# STM32F4_Control_Board.net
KiCad netlist of a schematic drawn in Altium Designer
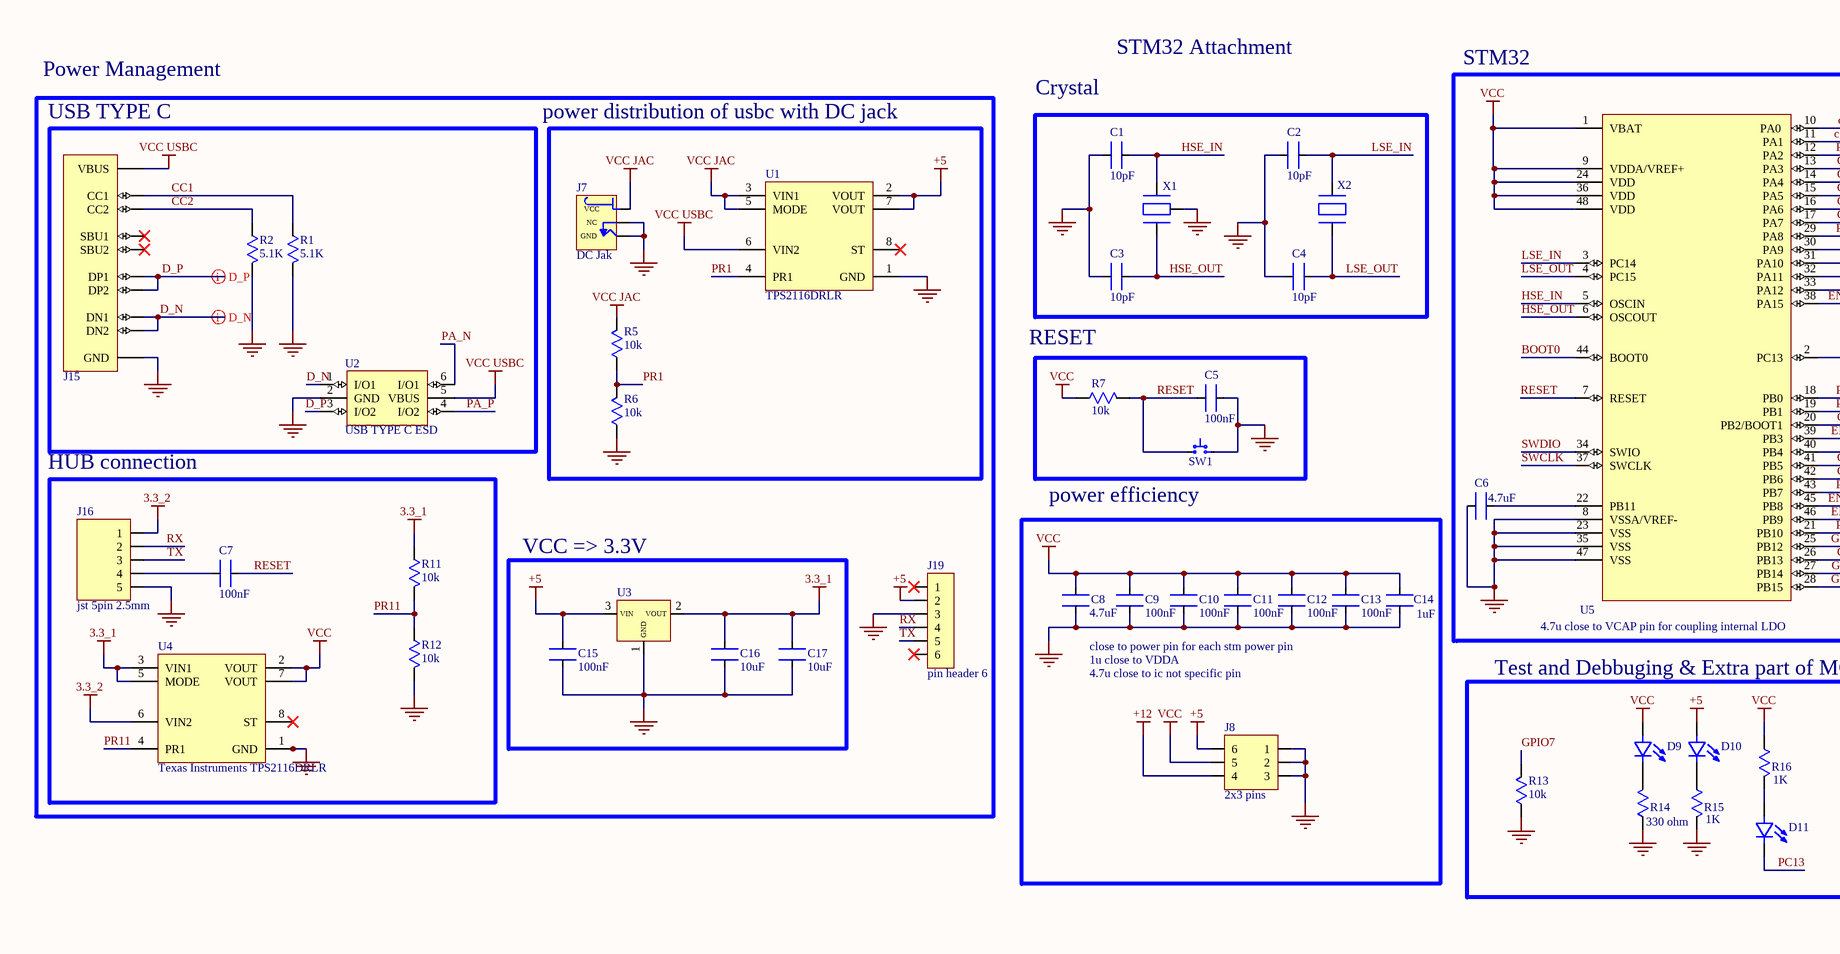
[diagram p0: STM32F4 Control Board.SchDoc, left]
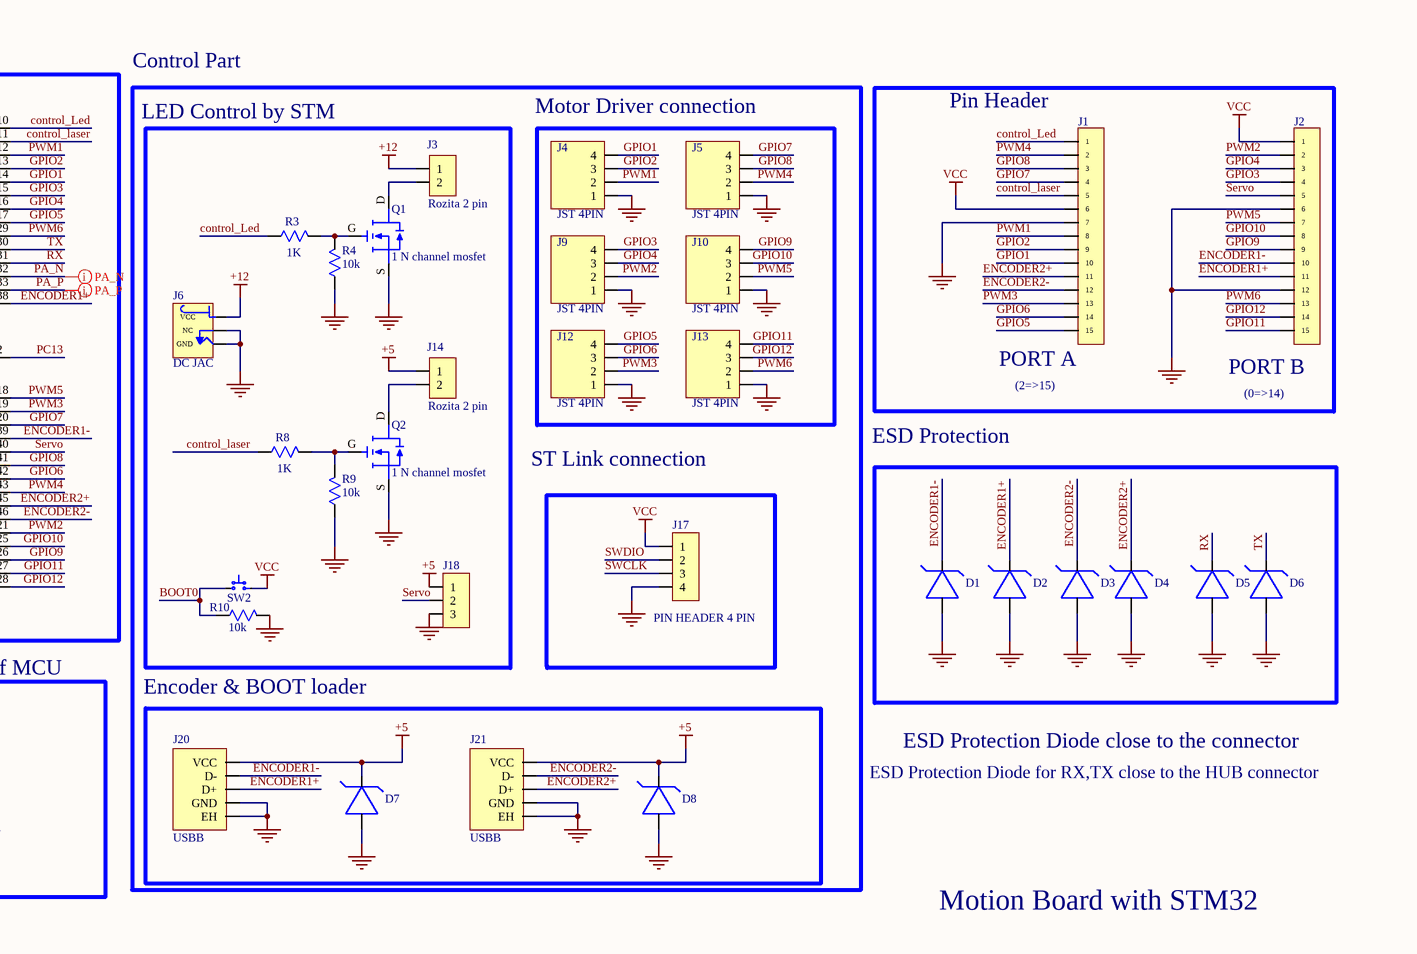
[diagram p1: STM32F4 Control Board.SchDoc, right]

(export (version "E")
  (design (tool "Eeschema 10.0.6"))
  (components
    (comp (ref "C1")
      (value "10pF")
      (footprint "0603 CAP")
      (description "50V 10pF NP0 ±5% 0603 Multilayer Ceramic Capacitors MLCC - SMD/SMT ROHS")
      (fields (field (name "MANUFACTURE PART NUMBER") "CC0603JRNPO9BN100"))
      (libsource (lib "control_ugvc") (part "10pF"))
    )
    (comp (ref "C2")
      (value "10pF")
      (footprint "0603 CAP")
      (description "50V 10pF NP0 ±5% 0603 Multilayer Ceramic Capacitors MLCC - SMD/SMT ROHS")
      (fields (field (name "MANUFACTURE PART NUMBER") "CC0603JRNPO9BN100"))
      (libsource (lib "control_ugvc") (part "10pF"))
    )
    (comp (ref "C3")
      (value "10pF")
      (footprint "0603 CAP")
      (description "50V 10pF NP0 ±5% 0603 Multilayer Ceramic Capacitors MLCC - SMD/SMT ROHS")
      (fields (field (name "MANUFACTURE PART NUMBER") "CC0603JRNPO9BN100"))
      (libsource (lib "control_ugvc") (part "10pF"))
    )
    (comp (ref "C4")
      (value "10pF")
      (footprint "0603 CAP")
      (description "50V 10pF NP0 ±5% 0603 Multilayer Ceramic Capacitors MLCC - SMD/SMT ROHS")
      (fields (field (name "MANUFACTURE PART NUMBER") "CC0603JRNPO9BN100"))
      (libsource (lib "control_ugvc") (part "10pF"))
    )
    (comp (ref "C5")
      (value "100nF")
      (footprint "0603 CAP")
      (description "50V 100nF X7R ±10% 0603 Multilayer Ceramic Capacitors MLCC - SMD/SMT ROHS")
      (fields (field (name "MANUFACTURE PART NUMBER") "CC0603KRX7R9BB104"))
      (libsource (lib "control_ugvc") (part "100nF"))
    )
    (comp (ref "C6")
      (value "4.7uF")
      (footprint "0603 CAP")
      (description "6.3V 4.7uF X5R ±20% 0603 Multilayer Ceramic Capacitors MLCC - SMD/SMT ROHS")
      (fields (field (name "MANUFACTURE PART NUMBER") "CL10A475MQ8NNNC"))
      (libsource (lib "control_ugvc") (part "4.7uF"))
    )
    (comp (ref "C7")
      (value "100nF")
      (footprint "0603 CAP")
      (description "50V 100nF X7R ±10% 0603 Multilayer Ceramic Capacitors MLCC - SMD/SMT ROHS")
      (fields (field (name "MANUFACTURE PART NUMBER") "CC0603KRX7R9BB104"))
      (libsource (lib "control_ugvc") (part "100nF"))
    )
    (comp (ref "C8")
      (value "4.7uF")
      (footprint "0603 CAP")
      (description "6.3V 4.7uF X5R ±20% 0603 Multilayer Ceramic Capacitors MLCC - SMD/SMT ROHS")
      (fields (field (name "MANUFACTURE PART NUMBER") "CL10A475MQ8NNNC"))
      (libsource (lib "control_ugvc") (part "4.7uF"))
    )
    (comp (ref "C9")
      (value "100nF")
      (footprint "0603 CAP")
      (description "50V 100nF X7R ±10% 0603 Multilayer Ceramic Capacitors MLCC - SMD/SMT ROHS")
      (fields (field (name "MANUFACTURE PART NUMBER") "CC0603KRX7R9BB104"))
      (libsource (lib "control_ugvc") (part "100nF"))
    )
    (comp (ref "C10")
      (value "100nF")
      (footprint "0603 CAP")
      (description "50V 100nF X7R ±10% 0603 Multilayer Ceramic Capacitors MLCC - SMD/SMT ROHS")
      (fields (field (name "MANUFACTURE PART NUMBER") "CC0603KRX7R9BB104"))
      (libsource (lib "control_ugvc") (part "100nF"))
    )
    (comp (ref "C11")
      (value "100nF")
      (footprint "0603 CAP")
      (description "50V 100nF X7R ±10% 0603 Multilayer Ceramic Capacitors MLCC - SMD/SMT ROHS")
      (fields (field (name "MANUFACTURE PART NUMBER") "CC0603KRX7R9BB104"))
      (libsource (lib "control_ugvc") (part "100nF"))
    )
    (comp (ref "C12")
      (value "100nF")
      (footprint "0603 CAP")
      (description "50V 100nF X7R ±10% 0603 Multilayer Ceramic Capacitors MLCC - SMD/SMT ROHS")
      (fields (field (name "MANUFACTURE PART NUMBER") "CC0603KRX7R9BB104"))
      (libsource (lib "control_ugvc") (part "100nF"))
    )
    (comp (ref "C13")
      (value "100nF")
      (footprint "0603 CAP")
      (description "50V 100nF X7R ±10% 0603 Multilayer Ceramic Capacitors MLCC - SMD/SMT ROHS")
      (fields (field (name "MANUFACTURE PART NUMBER") "CC0603KRX7R9BB104"))
      (libsource (lib "control_ugvc") (part "100nF"))
    )
    (comp (ref "C14")
      (value "1uF")
      (footprint "0603 CAP")
      (description "16V 1uF X5R ±10% 0603 Multilayer Ceramic Capacitors MLCC - SMD/SMT ROHS")
      (fields (field (name "MANUFACTURE PART NUMBER") "CGA0603X5R105K160JT"))
      (libsource (lib "control_ugvc") (part "1uF"))
    )
    (comp (ref "C15")
      (value "100nF")
      (footprint "0603 CAP")
      (description "50V 100nF X7R ±10% 0603 Multilayer Ceramic Capacitors MLCC - SMD/SMT ROHS")
      (fields (field (name "MANUFACTURE PART NUMBER") "CC0603KRX7R9BB104"))
      (libsource (lib "control_ugvc") (part "100nF"))
    )
    (comp (ref "C16")
      (value "10uF")
      (footprint "0603 CAP")
      (description "6.3V 10uF X5R ±20% 0603 Multilayer Ceramic Capacitors MLCC - SMD/SMT ROHS")
      (fields (field (name "MANUFACTURE PART NUMBER") "CC0603MRX5R5BB106"))
      (libsource (lib "control_ugvc") (part "10uF"))
    )
    (comp (ref "C17")
      (value "10uF")
      (footprint "0603 CAP")
      (description "6.3V 10uF X5R ±20% 0603 Multilayer Ceramic Capacitors MLCC - SMD/SMT ROHS")
      (fields (field (name "MANUFACTURE PART NUMBER") "CC0603MRX5R5BB106"))
      (libsource (lib "control_ugvc") (part "10uF"))
    )
    (comp (ref "D1")
      (value "ESD protection diode")
      (footprint "ESD protection diode")
      (description "SOT-5X3 ESD and Surge Protection (TVS/ESD) ROHS")
      (fields (field (name "MANUFACTURE PART NUMBER") "ESD321DYAR"))
      (libsource (lib "control_ugvc") (part "ESD protection diode"))
    )
    (comp (ref "D2")
      (value "ESD protection diode")
      (footprint "ESD protection diode")
      (description "SOT-5X3 ESD and Surge Protection (TVS/ESD) ROHS")
      (fields (field (name "MANUFACTURE PART NUMBER") "ESD321DYAR"))
      (libsource (lib "control_ugvc") (part "ESD protection diode"))
    )
    (comp (ref "D3")
      (value "ESD protection diode")
      (footprint "ESD protection diode")
      (description "SOT-5X3 ESD and Surge Protection (TVS/ESD) ROHS")
      (fields (field (name "MANUFACTURE PART NUMBER") "ESD321DYAR"))
      (libsource (lib "control_ugvc") (part "ESD protection diode"))
    )
    (comp (ref "D4")
      (value "ESD protection diode")
      (footprint "ESD protection diode")
      (description "SOT-5X3 ESD and Surge Protection (TVS/ESD) ROHS")
      (fields (field (name "MANUFACTURE PART NUMBER") "ESD321DYAR"))
      (libsource (lib "control_ugvc") (part "ESD protection diode"))
    )
    (comp (ref "D5")
      (value "ESD protection diode")
      (footprint "ESD protection diode")
      (description "SOT-5X3 ESD and Surge Protection (TVS/ESD) ROHS")
      (fields (field (name "MANUFACTURE PART NUMBER") "ESD321DYAR"))
      (libsource (lib "control_ugvc") (part "ESD protection diode"))
    )
    (comp (ref "D6")
      (value "ESD protection diode")
      (footprint "ESD protection diode")
      (description "SOT-5X3 ESD and Surge Protection (TVS/ESD) ROHS")
      (fields (field (name "MANUFACTURE PART NUMBER") "ESD321DYAR"))
      (libsource (lib "control_ugvc") (part "ESD protection diode"))
    )
    (comp (ref "D7")
      (value "ESD protection diode")
      (footprint "ESD protection diode")
      (description "SOT-5X3 ESD and Surge Protection (TVS/ESD) ROHS")
      (fields (field (name "MANUFACTURE PART NUMBER") "ESD321DYAR"))
      (libsource (lib "control_ugvc") (part "ESD protection diode"))
    )
    (comp (ref "D8")
      (value "ESD protection diode")
      (footprint "ESD protection diode")
      (description "SOT-5X3 ESD and Surge Protection (TVS/ESD) ROHS")
      (fields (field (name "MANUFACTURE PART NUMBER") "ESD321DYAR"))
      (libsource (lib "control_ugvc") (part "ESD protection diode"))
    )
    (comp (ref "D9")
      (value "RED led")
      (footprint "led 0805")
      (description "20mA 8mcd Colorless Transparent Lens 617nm Red 2V 0805 LED Indication - Discrete ROHS")
      (fields (field (name "MANUFACTURE PART NUMBER") "APT2012EC"))
      (libsource (lib "control_ugvc") (part "RED LED"))
    )
    (comp (ref "D10")
      (value "RED led")
      (footprint "led 0805")
      (description "20mA 8mcd Colorless Transparent Lens 617nm Red 2V 0805 LED Indication - Discrete ROHS")
      (fields (field (name "MANUFACTURE PART NUMBER") "APT2012EC"))
      (libsource (lib "control_ugvc") (part "RED LED"))
    )
    (comp (ref "D11")
      (value "RED led")
      (footprint "led 0805")
      (description "20mA 8mcd Colorless Transparent Lens 617nm Red 2V 0805 LED Indication - Discrete ROHS")
      (fields (field (name "MANUFACTURE PART NUMBER") "APT2012EC"))
      (libsource (lib "control_ugvc") (part "RED LED"))
    )
    (comp (ref "J1")
      (value "pin header 15 pin")
      (footprint "pin headers 15 pin")
      (fields (field (name "MANUFACTURE PART NUMBER") "ZX-PZ2.54-1-15PZZ"))
      (libsource (lib "control_ugvc") (part "pin header 15 pin"))
    )
    (comp (ref "J2")
      (value "pin header 15 pin")
      (footprint "pin headers 15 pin")
      (fields (field (name "MANUFACTURE PART NUMBER") "ZX-PZ2.54-1-15PZZ"))
      (libsource (lib "control_ugvc") (part "pin header 15 pin"))
    )
    (comp (ref "J3")
      (value "Rozita 2 pin")
      (footprint "Rozita")
      (fields (field (name "MANUFACTURE PART NUMBER") "DB128L-5.08-2P-GN-S"))
      (libsource (lib "control_ugvc") (part "Rozita 2 pin"))
    )
    (comp (ref "J4")
      (value "JST 4PIN")
      (footprint "JST 4PIN")
      (fields (field (name "MANUFACTURE PART NUMBER") "HC-XH-4A-TW"))
      (libsource (lib "control_ugvc") (part "JST 4PIN"))
    )
    (comp (ref "J5")
      (value "JST 4PIN")
      (footprint "JST 4PIN")
      (fields (field (name "MANUFACTURE PART NUMBER") "HC-XH-4A-TW"))
      (libsource (lib "control_ugvc") (part "JST 4PIN"))
    )
    (comp (ref "J6")
      (value "DC JAC")
      (footprint "DC Jack")
      (description "Bend-in DC Power Receptacle -20℃~+70℃ 2.5mm 6.5mm 5A 24V Plugin DC Power Connectors ROHS")
      (fields (field (name "MANUFACTURE PART NUMBER") "DC-005-5A-2.5"))
      (libsource (lib "control_ugvc") (part "DC Jak"))
    )
    (comp (ref "J7")
      (value "DC Jak")
      (footprint "DC Jack")
      (description "Bend-in DC Power Receptacle -20℃~+70℃ 2.5mm 6.5mm 5A 24V Plugin DC Power Connectors ROHS")
      (fields (field (name "MANUFACTURE PART NUMBER") "DC-005-5A-2.5"))
      (libsource (lib "control_ugvc") (part "DC Jak"))
    )
    (comp (ref "J8")
      (value "2x3 pins")
      (footprint "2x3 pins")
      (description "Straight 2.54mm 6mm 6P 3mm 2.54mm 双排 2x3P Plugin,P=2.54mm Pin Headers ROHS")
      (fields (field (name "MANUFACTURER") "HanElectricity") (field (name "MFR. PART #") "2541WV-2x03P"))
      (libsource (lib "control_ugvc") (part "2x3 pins"))
    )
    (comp (ref "J9")
      (value "JST 4PIN")
      (footprint "JST 4PIN")
      (fields (field (name "MANUFACTURE PART NUMBER") "HC-XH-4A-TW"))
      (libsource (lib "control_ugvc") (part "JST 4PIN"))
    )
    (comp (ref "J10")
      (value "JST 4PIN")
      (footprint "JST 4PIN")
      (fields (field (name "MANUFACTURE PART NUMBER") "HC-XH-4A-TW"))
      (libsource (lib "control_ugvc") (part "JST 4PIN"))
    )
    (comp (ref "J12")
      (value "JST 4PIN")
      (footprint "JST 4PIN")
      (fields (field (name "MANUFACTURE PART NUMBER") "HC-XH-4A-TW"))
      (libsource (lib "control_ugvc") (part "JST 4PIN"))
    )
    (comp (ref "J13")
      (value "JST 4PIN")
      (footprint "JST 4PIN")
      (fields (field (name "MANUFACTURE PART NUMBER") "HC-XH-4A-TW"))
      (libsource (lib "control_ugvc") (part "JST 4PIN"))
    )
    (comp (ref "J14")
      (value "Rozita 2 pin")
      (footprint "Rozita")
      (fields (field (name "MANUFACTURE PART NUMBER") "DB128L-5.08-2P-GN-S"))
      (libsource (lib "control_ugvc") (part "Rozita 2 pin"))
    )
    (comp (ref "J15")
      (value "USB TYPE-C-31-M-12")
      (footprint "USB Type-C")
      (description "5A 1 16P Female Type-C SMD USB Connectors ROHS")
      (fields (field (name "MANUFACTURE PART NUMBER") "TYPE-C-31-M-12"))
      (libsource (lib "control_ugvc") (part "USB TYPE-C-31-M-12"))
    )
    (comp (ref "J16")
      (value "jst 5pin 2.5mm")
      (footprint "JST 5 PIN 2.5 MM")
      (fields (field (name "MANUFACTURE PART NUMBER") "B5B-XH-A(LF)(SN)"))
      (libsource (lib "control_ugvc") (part "jst 5pin 2.5mm"))
    )
    (comp (ref "J17")
      (value "PIN HEADER 4 PIN")
      (footprint "pin header 4PIN")
      (description "3A Policy 2.5mm 6mm 4P -40℃~+105℃ 2.54mm Single Row 1x4P Plugin,P=2.54mm Pin Headers ROHS")
      (fields (field (name "MANUFACTURE PART NUMBER") "A254UP-ZD04P"))
      (libsource (lib "control_ugvc") (part "PIN HEADER 4 PIN"))
    )
    (comp (ref "J18")
      (value "Plugin,P=2.54mm")
      (footprint "pin header 3 pin")
      (description "3A Straight 3P -65℃~+125℃ 2.54mm Black Single Row Phosphor Bronze Plugin,P=2.54mm Pin Headers ROHS")
      (fields (field (name "MANUFACTURE PART NUMBER") "68001-203HLF"))
      (libsource (lib "control_ugvc") (part "Pin Header 3pin"))
    )
    (comp (ref "J19")
      (value "pin header 6")
      (footprint "pin header 6 pin")
      (fields (field (name "MANUFACTURE PART NUMBER") "PZ254V-11-06P"))
      (libsource (lib "control_ugvc") (part "pin header 6"))
    )
    (comp (ref "J20")
      (value "USBB")
      (footprint "USBB")
      (description "USB 2.0 1 4P Female Type-B Plugin USB Connectors ROHS")
      (fields (field (name "MANUFACTURE PART NUMBER") "U-USBBR04P-F000"))
      (libsource (lib "control_ugvc") (part "USBB R04P-F000"))
    )
    (comp (ref "J21")
      (value "USBB")
      (footprint "USBB")
      (description "USB 2.0 1 4P Female Type-B Plugin USB Connectors ROHS")
      (fields (field (name "MANUFACTURE PART NUMBER") "U-USBBR04P-F000"))
      (libsource (lib "control_ugvc") (part "USBB R04P-F000"))
    )
    (comp (ref "Q1")
      (value "1 N channel mosfet")
      (footprint "1 N channel mosfet")
      (description "20V 7A 1.25W 10mΩ@4.5V,7A 500mV 1 N-channel SOT-23-3L MOSFETs ROHS")
      (fields (field (name "MANUFACTURE PART NUMBER") "SP20N09T1"))
      (libsource (lib "control_ugvc") (part "1 N channel mosfet"))
    )
    (comp (ref "Q2")
      (value "1 N channel mosfet")
      (footprint "1 N channel mosfet")
      (description "20V 7A 1.25W 10mΩ@4.5V,7A 500mV 1 N-channel SOT-23-3L MOSFETs ROHS")
      (fields (field (name "MANUFACTURE PART NUMBER") "SP20N09T1"))
      (libsource (lib "control_ugvc") (part "1 N channel mosfet"))
    )
    (comp (ref "R1")
      (value "5.1K")
      (footprint "0603 RES")
      (description "100mW Thin Film Resistor 75V ±25ppm/℃ ±0.1% 5.1kΩ 0603 Chip Resistor - Surface Mount ROHS")
      (fields (field (name "MANUFACTURE PART NUMBER") "RT0603BRD075K1L"))
      (libsource (lib "control_ugvc") (part "RES 5.1 K"))
    )
    (comp (ref "R2")
      (value "5.1K")
      (footprint "0603 RES")
      (description "100mW Thin Film Resistor 75V ±25ppm/℃ ±0.1% 5.1kΩ 0603 Chip Resistor - Surface Mount ROHS")
      (fields (field (name "MANUFACTURE PART NUMBER") "RT0603BRD075K1L"))
      (libsource (lib "control_ugvc") (part "RES 5.1 K"))
    )
    (comp (ref "R3")
      (value "1K")
      (footprint "0603 RES")
      (description "100mW Thick Film Resistors 75V ±100ppm/℃ ±5% 1kΩ 0603 Chip Resistor - Surface Mount ROHS")
      (fields (field (name "MANUFACTURE PART NUMBER") "FRC0603J102 TS"))
      (libsource (lib "control_ugvc") (part "RES 1K ohm"))
    )
    (comp (ref "R4")
      (value "10k")
      (footprint "0603 RES")
      (description "100mW Thin Film Resistor 75V ±25ppm/℃ ±0.1% 10kΩ 0603 Chip Resistor - Surface Mount ROHS")
      (fields (field (name "MANUFACTURE PART NUMBER") "RT0603BRD0710KL"))
      (libsource (lib "control_ugvc") (part "RES 10kohm"))
    )
    (comp (ref "R5")
      (value "10k")
      (footprint "0603 RES")
      (description "100mW Thin Film Resistor 75V ±25ppm/℃ ±0.1% 10kΩ 0603 Chip Resistor - Surface Mount ROHS")
      (fields (field (name "MANUFACTURE PART NUMBER") "RT0603BRD0710KL"))
      (libsource (lib "control_ugvc") (part "RES 10kohm"))
    )
    (comp (ref "R6")
      (value "10k")
      (footprint "0603 RES")
      (description "100mW Thin Film Resistor 75V ±25ppm/℃ ±0.1% 10kΩ 0603 Chip Resistor - Surface Mount ROHS")
      (fields (field (name "MANUFACTURE PART NUMBER") "RT0603BRD0710KL"))
      (libsource (lib "control_ugvc") (part "RES 10kohm"))
    )
    (comp (ref "R7")
      (value "10k")
      (footprint "0603 RES")
      (description "100mW Thin Film Resistor 75V ±25ppm/℃ ±0.1% 10kΩ 0603 Chip Resistor - Surface Mount ROHS")
      (fields (field (name "MANUFACTURE PART NUMBER") "RT0603BRD0710KL"))
      (libsource (lib "control_ugvc") (part "RES 10kohm"))
    )
    (comp (ref "R8")
      (value "1K")
      (footprint "0603 RES")
      (description "100mW Thick Film Resistors 75V ±100ppm/℃ ±5% 1kΩ 0603 Chip Resistor - Surface Mount ROHS")
      (fields (field (name "MANUFACTURE PART NUMBER") "FRC0603J102 TS"))
      (libsource (lib "control_ugvc") (part "RES 1K ohm"))
    )
    (comp (ref "R9")
      (value "10k")
      (footprint "0603 RES")
      (description "100mW Thin Film Resistor 75V ±25ppm/℃ ±0.1% 10kΩ 0603 Chip Resistor - Surface Mount ROHS")
      (fields (field (name "MANUFACTURE PART NUMBER") "RT0603BRD0710KL"))
      (libsource (lib "control_ugvc") (part "RES 10kohm"))
    )
    (comp (ref "R10")
      (value "10k")
      (footprint "0603 RES")
      (description "100mW Thin Film Resistor 75V ±25ppm/℃ ±0.1% 10kΩ 0603 Chip Resistor - Surface Mount ROHS")
      (fields (field (name "MANUFACTURE PART NUMBER") "RT0603BRD0710KL"))
      (libsource (lib "control_ugvc") (part "RES 10kohm"))
    )
    (comp (ref "R11")
      (value "10k")
      (footprint "0603 RES")
      (description "100mW Thin Film Resistor 75V ±25ppm/℃ ±0.1% 10kΩ 0603 Chip Resistor - Surface Mount ROHS")
      (fields (field (name "MANUFACTURE PART NUMBER") "RT0603BRD0710KL"))
      (libsource (lib "control_ugvc") (part "RES 10kohm"))
    )
    (comp (ref "R12")
      (value "10k")
      (footprint "0603 RES")
      (description "100mW Thin Film Resistor 75V ±25ppm/℃ ±0.1% 10kΩ 0603 Chip Resistor - Surface Mount ROHS")
      (fields (field (name "MANUFACTURE PART NUMBER") "RT0603BRD0710KL"))
      (libsource (lib "control_ugvc") (part "RES 10kohm"))
    )
    (comp (ref "R13")
      (value "10k")
      (footprint "0603 RES")
      (description "100mW Thin Film Resistor 75V ±25ppm/℃ ±0.1% 10kΩ 0603 Chip Resistor - Surface Mount ROHS")
      (fields (field (name "MANUFACTURE PART NUMBER") "RT0603BRD0710KL"))
      (libsource (lib "control_ugvc") (part "RES 10kohm"))
    )
    (comp (ref "R14")
      (value "330 ohm")
      (footprint "0603 RES")
      (description "100mW Thick Film Resistors 75V ±100ppm/℃ ±5% 330Ω 0603 Chip Resistor - Surface Mount ROHS")
      (fields (field (name "MANUFACTURE PART NUMBER") "FRC0603J331 TS"))
      (libsource (lib "control_ugvc") (part "RES 330 ohm"))
    )
    (comp (ref "R15")
      (value "1K")
      (footprint "0603 RES")
      (description "100mW Thick Film Resistors 75V ±100ppm/℃ ±5% 1kΩ 0603 Chip Resistor - Surface Mount ROHS")
      (fields (field (name "MANUFACTURE PART NUMBER") "FRC0603J102 TS"))
      (libsource (lib "control_ugvc") (part "RES 1K ohm"))
    )
    (comp (ref "R16")
      (value "1K")
      (footprint "0603 RES")
      (description "100mW Thick Film Resistors 75V ±100ppm/℃ ±5% 1kΩ 0603 Chip Resistor - Surface Mount ROHS")
      (fields (field (name "MANUFACTURE PART NUMBER") "FRC0603J102 TS"))
      (libsource (lib "control_ugvc") (part "RES 1K ohm"))
    )
    (comp (ref "SW1")
      (value "push button")
      (footprint "Push button")
      (fields (field (name "MANUFACTURE PART NUMBER") "1TS002E-2500-2500-CT"))
      (libsource (lib "control_ugvc") (part "push button"))
    )
    (comp (ref "SW2")
      (value "push button")
      (footprint "Push button")
      (fields (field (name "MANUFACTURE PART NUMBER") "1TS002E-2500-2500-CT"))
      (libsource (lib "control_ugvc") (part "push button"))
    )
    (comp (ref "U1")
      (value "TPS2116DRLR")
      (footprint "power distribution")
      (description "1.6V~5.5V 42mΩ 2.5A 1 SOT-583 Power Distribution Switches ROHS")
      (libsource (lib "control_ugvc") (part "power distribution"))
    )
    (comp (ref "U2")
      (value "USB TYPE C ESD")
      (footprint "usb c esd")
      (description "SOT-23-6 ESD and Surge Protection (TVS/ESD) ROHS")
      (fields (field (name "MANUFACTURE PART NUMBER") "TPUSBLC6-2SC6"))
      (libsource (lib "control_ugvc") (part "usb tybc esd"))
    )
    (comp (ref "U3")
      (value "ST LDO 3.3 regulator")
      (footprint "ST_LDO")
      (fields (field (name "MANUFACTURE PART NUMBER") "LD1117AS33TR"))
      (libsource (lib "control_ugvc") (part "ST LDO 3.3 regulator"))
    )
    (comp (ref "U4")
      (value "Texas Instruments TPS2116DRLR")
      (footprint "power distribution")
      (description "1.6V~5.5V 42mΩ 2.5A 1 SOT-583 Power Distribution Switches ROHS")
      (fields (field (name "MANUFACTURE PART NUMBER") "TPS2116DRLR"))
      (libsource (lib "control_ugvc") (part "power distribution"))
    )
    (comp (ref "U5")
      (value "High-performance basic series ARM Cortex-M4 MCU with DSP and FPU, featuring 512 KB Flash, 100 MHz CPU, and ART accelerator")
      (footprint "Stm32 UFQFPN-48")
      (description "ARM-M4 100MHz UFQFPN-48(7x7) Microcontrollers (MCU/MPU/SOC) ROHS")
      (fields (field (name "MANUFACTURE  PART NUMBER") "STM32F411CEU6"))
      (libsource (lib "control_ugvc") (part "STMicroelectronics STM32F411CEU6"))
    )
    (comp (ref "X1")
      (value "Shenzhen SCTF Elec SX3B25.000F0810G30")
      (footprint "25MHZ Crystal Oscillators")
      (description "25MHz Surface Mount Crystal 8pF ±10ppm ±30ppm SMD3225-4P Crystals ROHS")
      (fields (field (name "MANUFACTURE PART NUMBER") "SX3B25.000F0810G30"))
      (libsource (lib "control_ugvc") (part "25MHZ Crystal oscillator"))
    )
    (comp (ref "X2")
      (value "Seiko Epson X1A0000610006")
      (footprint "32.768 KHZ Crystal oscillator")
      (description "32.768kHz Surface Mount Crystal 7pF ±20ppm SMD2012-2P Crystals ROHSS.")
      (fields (field (name "MANUFACTURE PART NUMBER") "X1A0000610006"))
      (libsource (lib "control_ugvc") (part "32.768 KHZ Crystal oscillator"))
    )
  )
  (nets
    (net (code "1") (name "+5") (class "Default")
      (node (ref "C15") (pin "2") (pinfunction "2_2") (pintype "passive"))
      (node (ref "D10") (pin "1") (pinfunction "1_1") (pintype "passive"))
      (node (ref "D7") (pin "2") (pinfunction "2_2") (pintype "passive"))
      (node (ref "D8") (pin "2") (pinfunction "2_2") (pintype "passive"))
      (node (ref "J14") (pin "1") (pinfunction "1_1") (pintype "passive"))
      (node (ref "J18") (pin "1") (pinfunction "1_1") (pintype "passive"))
      (node (ref "J19") (pin "2") (pinfunction "2_2") (pintype "passive"))
      (node (ref "J20") (pin "1") (pinfunction "VCC_1") (pintype "power_in"))
      (node (ref "J21") (pin "1") (pinfunction "VCC_1") (pintype "power_in"))
      (node (ref "J8") (pin "6") (pinfunction "6_6") (pintype "passive"))
      (node (ref "U1") (pin "2") (pinfunction "VOUT_2") (pintype "power_in"))
      (node (ref "U1") (pin "7") (pinfunction "VOUT_7") (pintype "power_in"))
      (node (ref "U3") (pin "3") (pinfunction "VIN_3") (pintype "power_in"))
    )
    (net (code "2") (name "+12") (class "Default")
      (node (ref "J3") (pin "1") (pinfunction "1_1") (pintype "passive"))
      (node (ref "J6") (pin "1") (pinfunction "VCC_1") (pintype "power_in"))
      (node (ref "J8") (pin "4") (pinfunction "4_4") (pintype "passive"))
    )
    (net (code "3") (name "/BOOT0") (class "Default")
      (node (ref "R10") (pin "1") (pinfunction "1_1") (pintype "passive"))
      (node (ref "SW2") (pin "1") (pinfunction "1_1") (pintype "passive"))
      (node (ref "U5") (pin "44") (pinfunction "BOOT0_44") (pintype "bidirectional"))
    )
    (net (code "4") (name "/CC1") (class "Default")
      (node (ref "J15") (pin "A5") (pinfunction "CC1_A5") (pintype "bidirectional"))
      (node (ref "R1") (pin "1") (pinfunction "1_1") (pintype "passive"))
    )
    (net (code "5") (name "/CC2") (class "Default")
      (node (ref "J15") (pin "B5") (pinfunction "CC2_B5") (pintype "bidirectional"))
      (node (ref "R2") (pin "1") (pinfunction "1_1") (pintype "passive"))
    )
    (net (code "6") (name "/D_N") (class "Default")
      (node (ref "J15") (pin "A7") (pinfunction "DN1_A7") (pintype "bidirectional"))
      (node (ref "J15") (pin "B7") (pinfunction "DN2_B7") (pintype "bidirectional"))
      (node (ref "U2") (pin "1") (pinfunction "I/O1_1") (pintype "bidirectional"))
    )
    (net (code "7") (name "/D_P") (class "Default")
      (node (ref "J15") (pin "A6") (pinfunction "DP1_A6") (pintype "bidirectional"))
      (node (ref "J15") (pin "B6") (pinfunction "DP2_B6") (pintype "bidirectional"))
      (node (ref "U2") (pin "3") (pinfunction "I/O2_3") (pintype "bidirectional"))
    )
    (net (code "8") (name "/ENCODER1+") (class "Default")
      (node (ref "D2") (pin "2") (pinfunction "2_2") (pintype "passive"))
      (node (ref "J2") (pin "11") (pinfunction "11_11") (pintype "passive"))
      (node (ref "J20") (pin "3") (pinfunction "D+_3") (pintype "bidirectional"))
      (node (ref "U5") (pin "38") (pinfunction "PA15_38") (pintype "bidirectional"))
    )
    (net (code "9") (name "/ENCODER1-") (class "Default")
      (node (ref "D1") (pin "2") (pinfunction "2_2") (pintype "passive"))
      (node (ref "J2") (pin "10") (pinfunction "10_10") (pintype "passive"))
      (node (ref "J20") (pin "2") (pinfunction "D-_2") (pintype "bidirectional"))
      (node (ref "U5") (pin "39") (pinfunction "PB3_39") (pintype "bidirectional"))
    )
    (net (code "10") (name "/ENCODER2+") (class "Default")
      (node (ref "D4") (pin "2") (pinfunction "2_2") (pintype "passive"))
      (node (ref "J1") (pin "11") (pinfunction "11_11") (pintype "passive"))
      (node (ref "J21") (pin "3") (pinfunction "D+_3") (pintype "bidirectional"))
      (node (ref "U5") (pin "45") (pinfunction "PB8_45") (pintype "bidirectional"))
    )
    (net (code "11") (name "/ENCODER2-") (class "Default")
      (node (ref "D3") (pin "2") (pinfunction "2_2") (pintype "passive"))
      (node (ref "J1") (pin "12") (pinfunction "12_12") (pintype "passive"))
      (node (ref "J21") (pin "2") (pinfunction "D-_2") (pintype "bidirectional"))
      (node (ref "U5") (pin "46") (pinfunction "PB9_46") (pintype "bidirectional"))
    )
    (net (code "12") (name "/GPIO1") (class "Default")
      (node (ref "J1") (pin "10") (pinfunction "10_10") (pintype "passive"))
      (node (ref "J4") (pin "4") (pinfunction "4_4") (pintype "passive"))
      (node (ref "U5") (pin "14") (pinfunction "PA4_14") (pintype "bidirectional"))
    )
    (net (code "13") (name "/GPIO2") (class "Default")
      (node (ref "J1") (pin "9") (pinfunction "9_9") (pintype "passive"))
      (node (ref "J4") (pin "3") (pinfunction "3_3") (pintype "passive"))
      (node (ref "U5") (pin "13") (pinfunction "PA3_13") (pintype "bidirectional"))
    )
    (net (code "14") (name "/GPIO3") (class "Default")
      (node (ref "J2") (pin "4") (pinfunction "4_4") (pintype "passive"))
      (node (ref "J9") (pin "4") (pinfunction "4_4") (pintype "passive"))
      (node (ref "U5") (pin "15") (pinfunction "PA5_15") (pintype "bidirectional"))
    )
    (net (code "15") (name "/GPIO4") (class "Default")
      (node (ref "J2") (pin "3") (pinfunction "3_3") (pintype "passive"))
      (node (ref "J9") (pin "3") (pinfunction "3_3") (pintype "passive"))
      (node (ref "U5") (pin "16") (pinfunction "PA6_16") (pintype "bidirectional"))
    )
    (net (code "16") (name "/GPIO5") (class "Default")
      (node (ref "J1") (pin "15") (pinfunction "15_15") (pintype "passive"))
      (node (ref "J12") (pin "4") (pinfunction "4_4") (pintype "passive"))
      (node (ref "U5") (pin "17") (pinfunction "PA7_17") (pintype "bidirectional"))
    )
    (net (code "17") (name "/GPIO6") (class "Default")
      (node (ref "J1") (pin "14") (pinfunction "14_14") (pintype "passive"))
      (node (ref "J12") (pin "3") (pinfunction "3_3") (pintype "passive"))
      (node (ref "U5") (pin "42") (pinfunction "PB6_42") (pintype "bidirectional"))
    )
    (net (code "18") (name "/GPIO7") (class "Default")
      (node (ref "J1") (pin "4") (pinfunction "4_4") (pintype "passive"))
      (node (ref "J5") (pin "4") (pinfunction "4_4") (pintype "passive"))
      (node (ref "R13") (pin "2") (pinfunction "2_2") (pintype "passive"))
      (node (ref "U5") (pin "20") (pinfunction "PB2/BOOT1_20") (pintype "bidirectional"))
    )
    (net (code "19") (name "/GPIO8") (class "Default")
      (node (ref "J1") (pin "3") (pinfunction "3_3") (pintype "passive"))
      (node (ref "J5") (pin "3") (pinfunction "3_3") (pintype "passive"))
      (node (ref "U5") (pin "41") (pinfunction "PB5_41") (pintype "bidirectional"))
    )
    (net (code "20") (name "/GPIO9") (class "Default")
      (node (ref "J10") (pin "4") (pinfunction "4_4") (pintype "passive"))
      (node (ref "J2") (pin "9") (pinfunction "9_9") (pintype "passive"))
      (node (ref "U5") (pin "26") (pinfunction "PB13_26") (pintype "bidirectional"))
    )
    (net (code "21") (name "/GPIO10") (class "Default")
      (node (ref "J10") (pin "3") (pinfunction "3_3") (pintype "passive"))
      (node (ref "J2") (pin "8") (pinfunction "8_8") (pintype "passive"))
      (node (ref "U5") (pin "25") (pinfunction "PB12_25") (pintype "bidirectional"))
    )
    (net (code "22") (name "/GPIO11") (class "Default")
      (node (ref "J13") (pin "4") (pinfunction "4_4") (pintype "passive"))
      (node (ref "J2") (pin "15") (pinfunction "15_15") (pintype "passive"))
      (node (ref "U5") (pin "27") (pinfunction "PB14_27") (pintype "bidirectional"))
    )
    (net (code "23") (name "/GPIO12") (class "Default")
      (node (ref "J13") (pin "3") (pinfunction "3_3") (pintype "passive"))
      (node (ref "J2") (pin "14") (pinfunction "14_14") (pintype "passive"))
      (node (ref "U5") (pin "28") (pinfunction "PB15_28") (pintype "bidirectional"))
    )
    (net (code "24") (name "/HSE_IN") (class "Default")
      (node (ref "C1") (pin "1") (pinfunction "1_1") (pintype "passive"))
      (node (ref "U5") (pin "5") (pinfunction "OSCIN_5") (pintype "bidirectional"))
      (node (ref "X1") (pin "1") (pinfunction "OSC1_1") (pintype "passive"))
    )
    (net (code "25") (name "/HSE_OUT") (class "Default")
      (node (ref "C3") (pin "1") (pinfunction "1_1") (pintype "passive"))
      (node (ref "U5") (pin "6") (pinfunction "OSCOUT_6") (pintype "bidirectional"))
      (node (ref "X1") (pin "3") (pinfunction "OSC2_3") (pintype "passive"))
    )
    (net (code "26") (name "/LSE_IN") (class "Default")
      (node (ref "C2") (pin "1") (pinfunction "1_1") (pintype "passive"))
      (node (ref "U5") (pin "3") (pinfunction "PC14_3") (pintype "bidirectional"))
      (node (ref "X2") (pin "1") (pinfunction "OSC1_1") (pintype "passive"))
    )
    (net (code "27") (name "/LSE_OUT") (class "Default")
      (node (ref "C4") (pin "1") (pinfunction "1_1") (pintype "passive"))
      (node (ref "U5") (pin "4") (pinfunction "PC15_4") (pintype "bidirectional"))
      (node (ref "X2") (pin "2") (pinfunction "OSC2_2") (pintype "passive"))
    )
    (net (code "28") (name "/PA_N") (class "Default")
      (node (ref "U2") (pin "6") (pinfunction "I/O1_6") (pintype "bidirectional"))
      (node (ref "U5") (pin "32") (pinfunction "PA11_32") (pintype "bidirectional"))
    )
    (net (code "29") (name "/PA_P") (class "Default")
      (node (ref "U2") (pin "4") (pinfunction "I/O2_4") (pintype "bidirectional"))
      (node (ref "U5") (pin "33") (pinfunction "PA12_33") (pintype "bidirectional"))
    )
    (net (code "30") (name "/PC13") (class "Default")
      (node (ref "D11") (pin "2") (pinfunction "2_2") (pintype "passive"))
      (node (ref "U5") (pin "2") (pinfunction "PC13_2") (pintype "bidirectional"))
    )
    (net (code "31") (name "/PR1") (class "Default")
      (node (ref "R5") (pin "1") (pinfunction "1_1") (pintype "passive"))
      (node (ref "R6") (pin "2") (pinfunction "2_2") (pintype "passive"))
      (node (ref "U1") (pin "4") (pinfunction "PR1_4") (pintype "passive"))
    )
    (net (code "32") (name "/PR11") (class "Default")
      (node (ref "R11") (pin "1") (pinfunction "1_1") (pintype "passive"))
      (node (ref "R12") (pin "2") (pinfunction "2_2") (pintype "passive"))
      (node (ref "U4") (pin "4") (pinfunction "PR1_4") (pintype "passive"))
    )
    (net (code "33") (name "/PWM1") (class "Default")
      (node (ref "J1") (pin "8") (pinfunction "8_8") (pintype "passive"))
      (node (ref "J4") (pin "2") (pinfunction "2_2") (pintype "passive"))
      (node (ref "U5") (pin "12") (pinfunction "PA2_12") (pintype "bidirectional"))
    )
    (net (code "34") (name "/PWM2") (class "Default")
      (node (ref "J2") (pin "2") (pinfunction "2_2") (pintype "passive"))
      (node (ref "J9") (pin "2") (pinfunction "2_2") (pintype "passive"))
      (node (ref "U5") (pin "21") (pinfunction "PB10_21") (pintype "bidirectional"))
    )
    (net (code "35") (name "/PWM3") (class "Default")
      (node (ref "J1") (pin "13") (pinfunction "13_13") (pintype "passive"))
      (node (ref "J12") (pin "2") (pinfunction "2_2") (pintype "passive"))
      (node (ref "U5") (pin "19") (pinfunction "PB1_19") (pintype "bidirectional"))
    )
    (net (code "36") (name "/PWM4") (class "Default")
      (node (ref "J1") (pin "2") (pinfunction "2_2") (pintype "passive"))
      (node (ref "J5") (pin "2") (pinfunction "2_2") (pintype "passive"))
      (node (ref "U5") (pin "43") (pinfunction "PB7_43") (pintype "bidirectional"))
    )
    (net (code "37") (name "/PWM5") (class "Default")
      (node (ref "J10") (pin "2") (pinfunction "2_2") (pintype "passive"))
      (node (ref "J2") (pin "7") (pinfunction "7_7") (pintype "passive"))
      (node (ref "U5") (pin "18") (pinfunction "PB0_18") (pintype "bidirectional"))
    )
    (net (code "38") (name "/PWM6") (class "Default")
      (node (ref "J13") (pin "2") (pinfunction "2_2") (pintype "passive"))
      (node (ref "J2") (pin "13") (pinfunction "13_13") (pintype "passive"))
      (node (ref "U5") (pin "29") (pinfunction "PA8_29") (pintype "bidirectional"))
    )
    (net (code "39") (name "/RESET") (class "Default")
      (node (ref "C5") (pin "2") (pinfunction "2_2") (pintype "passive"))
      (node (ref "C7") (pin "2") (pinfunction "2_2") (pintype "passive"))
      (node (ref "R7") (pin "2") (pinfunction "2_2") (pintype "passive"))
      (node (ref "SW1") (pin "1") (pinfunction "1_1") (pintype "passive"))
      (node (ref "U5") (pin "7") (pinfunction "RESET_7") (pintype "bidirectional"))
    )
    (net (code "40") (name "/RX") (class "Default")
      (node (ref "D5") (pin "2") (pinfunction "2_2") (pintype "passive"))
      (node (ref "J16") (pin "2") (pinfunction "2_2") (pintype "passive"))
      (node (ref "J19") (pin "4") (pinfunction "4_4") (pintype "passive"))
      (node (ref "U5") (pin "31") (pinfunction "PA10_31") (pintype "bidirectional"))
    )
    (net (code "41") (name "/SWCLK") (class "Default")
      (node (ref "J17") (pin "3") (pinfunction "3_3") (pintype "passive"))
      (node (ref "U5") (pin "37") (pinfunction "SWCLK_37") (pintype "bidirectional"))
    )
    (net (code "42") (name "/SWDIO") (class "Default")
      (node (ref "J17") (pin "2") (pinfunction "2_2") (pintype "passive"))
      (node (ref "U5") (pin "34") (pinfunction "SWIO_34") (pintype "bidirectional"))
    )
    (net (code "43") (name "/Servo") (class "Default")
      (node (ref "J18") (pin "2") (pinfunction "2_2") (pintype "passive"))
      (node (ref "J2") (pin "5") (pinfunction "5_5") (pintype "passive"))
      (node (ref "U5") (pin "40") (pinfunction "PB4_40") (pintype "bidirectional"))
    )
    (net (code "44") (name "/TX") (class "Default")
      (node (ref "D6") (pin "2") (pinfunction "2_2") (pintype "passive"))
      (node (ref "J16") (pin "3") (pinfunction "3_3") (pintype "passive"))
      (node (ref "J19") (pin "5") (pinfunction "5_5") (pintype "passive"))
      (node (ref "U5") (pin "30") (pinfunction "PA9_30") (pintype "bidirectional"))
    )
    (net (code "45") (name "/control_Led") (class "Default")
      (node (ref "J1") (pin "1") (pinfunction "1_1") (pintype "passive"))
      (node (ref "R3") (pin "1") (pinfunction "1_1") (pintype "passive"))
      (node (ref "U5") (pin "10") (pinfunction "PA0_10") (pintype "bidirectional"))
    )
    (net (code "46") (name "/control_laser") (class "Default")
      (node (ref "J1") (pin "5") (pinfunction "5_5") (pintype "passive"))
      (node (ref "R8") (pin "1") (pinfunction "1_1") (pintype "passive"))
      (node (ref "U5") (pin "11") (pinfunction "PA1_11") (pintype "bidirectional"))
    )
    (net (code "47") (name "3.3_1") (class "Default")
      (node (ref "C16") (pin "1") (pinfunction "1_1") (pintype "passive"))
      (node (ref "C17") (pin "1") (pinfunction "1_1") (pintype "passive"))
      (node (ref "R11") (pin "2") (pinfunction "2_2") (pintype "passive"))
      (node (ref "U3") (pin "2") (pinfunction "VOUT_2") (pintype "power_in"))
      (node (ref "U4") (pin "3") (pinfunction "VIN1_3") (pintype "power_in"))
      (node (ref "U4") (pin "5") (pinfunction "MODE_5") (pintype "power_in"))
    )
    (net (code "48") (name "3.3_2") (class "Default")
      (node (ref "J16") (pin "1") (pinfunction "1_1") (pintype "passive"))
      (node (ref "U4") (pin "6") (pinfunction "VIN2_6") (pintype "power_in"))
    )
    (net (code "49") (name "GND") (class "Default")
      (node (ref "C1") (pin "2") (pinfunction "2_2") (pintype "passive"))
      (node (ref "C10") (pin "2") (pinfunction "2_2") (pintype "passive"))
      (node (ref "C11") (pin "2") (pinfunction "2_2") (pintype "passive"))
      (node (ref "C12") (pin "2") (pinfunction "2_2") (pintype "passive"))
      (node (ref "C13") (pin "2") (pinfunction "2_2") (pintype "passive"))
      (node (ref "C14") (pin "2") (pinfunction "2_2") (pintype "passive"))
      (node (ref "C15") (pin "1") (pinfunction "1_1") (pintype "passive"))
      (node (ref "C16") (pin "2") (pinfunction "2_2") (pintype "passive"))
      (node (ref "C17") (pin "2") (pinfunction "2_2") (pintype "passive"))
      (node (ref "C2") (pin "2") (pinfunction "2_2") (pintype "passive"))
      (node (ref "C3") (pin "2") (pinfunction "2_2") (pintype "passive"))
      (node (ref "C4") (pin "2") (pinfunction "2_2") (pintype "passive"))
      (node (ref "C5") (pin "1") (pinfunction "1_1") (pintype "passive"))
      (node (ref "C6") (pin "2") (pinfunction "2_2") (pintype "passive"))
      (node (ref "C8") (pin "1") (pinfunction "1_1") (pintype "passive"))
      (node (ref "C9") (pin "2") (pinfunction "2_2") (pintype "passive"))
      (node (ref "D1") (pin "1") (pinfunction "1_1") (pintype "passive"))
      (node (ref "D2") (pin "1") (pinfunction "1_1") (pintype "passive"))
      (node (ref "D3") (pin "1") (pinfunction "1_1") (pintype "passive"))
      (node (ref "D4") (pin "1") (pinfunction "1_1") (pintype "passive"))
      (node (ref "D5") (pin "1") (pinfunction "1_1") (pintype "passive"))
      (node (ref "D6") (pin "1") (pinfunction "1_1") (pintype "passive"))
      (node (ref "D7") (pin "1") (pinfunction "1_1") (pintype "passive"))
      (node (ref "D8") (pin "1") (pinfunction "1_1") (pintype "passive"))
      (node (ref "J1") (pin "7") (pinfunction "7_7") (pintype "passive"))
      (node (ref "J10") (pin "1") (pinfunction "1_1") (pintype "passive"))
      (node (ref "J12") (pin "1") (pinfunction "1_1") (pintype "passive"))
      (node (ref "J13") (pin "1") (pinfunction "1_1") (pintype "passive"))
      (node (ref "J15") (pin "0") (pinfunction "GND_0") (pintype "power_in"))
      (node (ref "J16") (pin "5") (pinfunction "5_5") (pintype "passive"))
      (node (ref "J17") (pin "4") (pinfunction "4_4") (pintype "passive"))
      (node (ref "J18") (pin "3") (pinfunction "3_3") (pintype "passive"))
      (node (ref "J19") (pin "3") (pinfunction "3_3") (pintype "passive"))
      (node (ref "J2") (pin "12") (pinfunction "12_12") (pintype "passive"))
      (node (ref "J2") (pin "6") (pinfunction "6_6") (pintype "passive"))
      (node (ref "J20") (pin "4") (pinfunction "GND_4") (pintype "power_in"))
      (node (ref "J20") (pin "5") (pinfunction "EH_5") (pintype "power_in"))
      (node (ref "J21") (pin "4") (pinfunction "GND_4") (pintype "power_in"))
      (node (ref "J21") (pin "5") (pinfunction "EH_5") (pintype "power_in"))
      (node (ref "J4") (pin "1") (pinfunction "1_1") (pintype "passive"))
      (node (ref "J5") (pin "1") (pinfunction "1_1") (pintype "passive"))
      (node (ref "J6") (pin "2") (pinfunction "GND_2") (pintype "power_in"))
      (node (ref "J6") (pin "3") (pinfunction "NC_3") (pintype "power_in"))
      (node (ref "J7") (pin "2") (pinfunction "GND_2") (pintype "power_in"))
      (node (ref "J7") (pin "3") (pinfunction "NC_3") (pintype "power_in"))
      (node (ref "J8") (pin "1") (pinfunction "1_1") (pintype "passive"))
      (node (ref "J8") (pin "2") (pinfunction "2_2") (pintype "passive"))
      (node (ref "J8") (pin "3") (pinfunction "3_3") (pintype "passive"))
      (node (ref "J9") (pin "1") (pinfunction "1_1") (pintype "passive"))
      (node (ref "Q1") (pin "S") (pinfunction "S_S") (pintype "passive"))
      (node (ref "Q2") (pin "S") (pinfunction "S_S") (pintype "passive"))
      (node (ref "R1") (pin "2") (pinfunction "2_2") (pintype "passive"))
      (node (ref "R10") (pin "2") (pinfunction "2_2") (pintype "passive"))
      (node (ref "R12") (pin "1") (pinfunction "1_1") (pintype "passive"))
      (node (ref "R13") (pin "1") (pinfunction "1_1") (pintype "passive"))
      (node (ref "R14") (pin "1") (pinfunction "1_1") (pintype "passive"))
      (node (ref "R15") (pin "2") (pinfunction "2_2") (pintype "passive"))
      (node (ref "R2") (pin "2") (pinfunction "2_2") (pintype "passive"))
      (node (ref "R4") (pin "1") (pinfunction "1_1") (pintype "passive"))
      (node (ref "R6") (pin "1") (pinfunction "1_1") (pintype "passive"))
      (node (ref "R9") (pin "1") (pinfunction "1_1") (pintype "passive"))
      (node (ref "SW1") (pin "2") (pinfunction "2_2") (pintype "passive"))
      (node (ref "U1") (pin "1") (pinfunction "GND_1") (pintype "power_in"))
      (node (ref "U2") (pin "2") (pinfunction "GND_2") (pintype "power_in"))
      (node (ref "U3") (pin "1") (pinfunction "GND_1") (pintype "power_in"))
      (node (ref "U4") (pin "1") (pinfunction "GND_1") (pintype "power_in"))
      (node (ref "U5") (pin "23") (pinfunction "VSS_23") (pintype "power_in"))
      (node (ref "U5") (pin "35") (pinfunction "VSS_35") (pintype "power_in"))
      (node (ref "U5") (pin "47") (pinfunction "VSS_47") (pintype "power_in"))
      (node (ref "U5") (pin "8") (pinfunction "VSSA/VREF-_8") (pintype "power_in"))
      (node (ref "X1") (pin "2") (pinfunction "GND_2") (pintype "passive"))
    )
    (net (code "50") (name "Net-(C7-Pad1)") (class "Default")
      (node (ref "C7") (pin "1") (pinfunction "1_1") (pintype "passive"))
      (node (ref "J16") (pin "4") (pinfunction "4_4") (pintype "passive"))
    )
    (net (code "51") (name "Net-(D9-Pad2)") (class "Default")
      (node (ref "D9") (pin "2") (pinfunction "2_2") (pintype "passive"))
      (node (ref "R14") (pin "2") (pinfunction "2_2") (pintype "passive"))
    )
    (net (code "52") (name "Net-(D10-Pad2)") (class "Default")
      (node (ref "D10") (pin "2") (pinfunction "2_2") (pintype "passive"))
      (node (ref "R15") (pin "1") (pinfunction "1_1") (pintype "passive"))
    )
    (net (code "53") (name "Net-(D11-Pad1)") (class "Default")
      (node (ref "D11") (pin "1") (pinfunction "1_1") (pintype "passive"))
      (node (ref "R16") (pin "2") (pinfunction "2_2") (pintype "passive"))
    )
    (net (code "54") (name "Net-(J3-Pad2)") (class "Default")
      (node (ref "J3") (pin "2") (pinfunction "2_2") (pintype "passive"))
      (node (ref "Q1") (pin "D") (pinfunction "D_D") (pintype "passive"))
    )
    (net (code "55") (name "Net-(J14-Pad2)") (class "Default")
      (node (ref "J14") (pin "2") (pinfunction "2_2") (pintype "passive"))
      (node (ref "Q2") (pin "D") (pinfunction "D_D") (pintype "passive"))
    )
    (net (code "56") (name "Net-(Q1-PadG)") (class "Default")
      (node (ref "Q1") (pin "G") (pinfunction "G_G") (pintype "passive"))
      (node (ref "R3") (pin "2") (pinfunction "2_2") (pintype "passive"))
      (node (ref "R4") (pin "2") (pinfunction "2_2") (pintype "passive"))
    )
    (net (code "57") (name "Net-(Q2-PadG)") (class "Default")
      (node (ref "Q2") (pin "G") (pinfunction "G_G") (pintype "passive"))
      (node (ref "R8") (pin "2") (pinfunction "2_2") (pintype "passive"))
      (node (ref "R9") (pin "2") (pinfunction "2_2") (pintype "passive"))
    )
    (net (code "58") (name "Net-(U5-PB11)") (class "Default")
      (node (ref "C6") (pin "1") (pinfunction "1_1") (pintype "passive"))
      (node (ref "U5") (pin "22") (pinfunction "PB11_22") (pintype "power_in"))
    )
    (net (code "59") (name "VCC") (class "Default")
      (node (ref "C10") (pin "1") (pinfunction "1_1") (pintype "passive"))
      (node (ref "C11") (pin "1") (pinfunction "1_1") (pintype "passive"))
      (node (ref "C12") (pin "1") (pinfunction "1_1") (pintype "passive"))
      (node (ref "C13") (pin "1") (pinfunction "1_1") (pintype "passive"))
      (node (ref "C14") (pin "1") (pinfunction "1_1") (pintype "passive"))
      (node (ref "C8") (pin "2") (pinfunction "2_2") (pintype "passive"))
      (node (ref "C9") (pin "1") (pinfunction "1_1") (pintype "passive"))
      (node (ref "D9") (pin "1") (pinfunction "1_1") (pintype "passive"))
      (node (ref "J1") (pin "6") (pinfunction "6_6") (pintype "passive"))
      (node (ref "J17") (pin "1") (pinfunction "1_1") (pintype "passive"))
      (node (ref "J2") (pin "1") (pinfunction "1_1") (pintype "passive"))
      (node (ref "J8") (pin "5") (pinfunction "5_5") (pintype "passive"))
      (node (ref "R16") (pin "1") (pinfunction "1_1") (pintype "passive"))
      (node (ref "R7") (pin "1") (pinfunction "1_1") (pintype "passive"))
      (node (ref "SW2") (pin "2") (pinfunction "2_2") (pintype "passive"))
      (node (ref "U4") (pin "2") (pinfunction "VOUT_2") (pintype "power_in"))
      (node (ref "U4") (pin "7") (pinfunction "VOUT_7") (pintype "power_in"))
      (node (ref "U5") (pin "1") (pinfunction "VBAT_1") (pintype "power_in"))
      (node (ref "U5") (pin "24") (pinfunction "VDD_24") (pintype "power_in"))
      (node (ref "U5") (pin "36") (pinfunction "VDD_36") (pintype "power_in"))
      (node (ref "U5") (pin "48") (pinfunction "VDD_48") (pintype "power_in"))
      (node (ref "U5") (pin "9") (pinfunction "VDDA/VREF+_9") (pintype "power_in"))
    )
    (net (code "60") (name "VCC JAC") (class "Default")
      (node (ref "J7") (pin "1") (pinfunction "VCC_1") (pintype "power_in"))
      (node (ref "R5") (pin "2") (pinfunction "2_2") (pintype "passive"))
      (node (ref "U1") (pin "3") (pinfunction "VIN1_3") (pintype "power_in"))
      (node (ref "U1") (pin "5") (pinfunction "MODE_5") (pintype "power_in"))
    )
    (net (code "61") (name "VCC USBC") (class "Default")
      (node (ref "J15") (pin "VBUS") (pinfunction "VBUS_VBUS") (pintype "power_in"))
      (node (ref "U1") (pin "6") (pinfunction "VIN2_6") (pintype "power_in"))
      (node (ref "U2") (pin "5") (pinfunction "VBUS_5") (pintype "power_in"))
    )
    (net (code "62") (name "unconnected-(J15-SBU1-PadA8)") (class "Default")
      (node (ref "J15") (pin "A8") (pinfunction "SBU1_A8") (pintype "bidirectional+no_connect"))
    )
    (net (code "63") (name "unconnected-(J15-SBU2-PadB8)") (class "Default")
      (node (ref "J15") (pin "B8") (pinfunction "SBU2_B8") (pintype "bidirectional+no_connect"))
    )
    (net (code "64") (name "unconnected-(J19-Pad1)") (class "Default")
      (node (ref "J19") (pin "1") (pinfunction "1_1") (pintype "passive+no_connect"))
    )
    (net (code "65") (name "unconnected-(J19-Pad6)") (class "Default")
      (node (ref "J19") (pin "6") (pinfunction "6_6") (pintype "passive+no_connect"))
    )
    (net (code "66") (name "unconnected-(U1-ST-Pad8)") (class "Default")
      (node (ref "U1") (pin "8") (pinfunction "ST_8") (pintype "open_collector+no_connect"))
    )
    (net (code "67") (name "unconnected-(U4-ST-Pad8)") (class "Default")
      (node (ref "U4") (pin "8") (pinfunction "ST_8") (pintype "open_collector+no_connect"))
    )
  )
)
